# RPi_SPI_outputs_v03.net
KiCad netlist of a schematic drawn in EAGLE
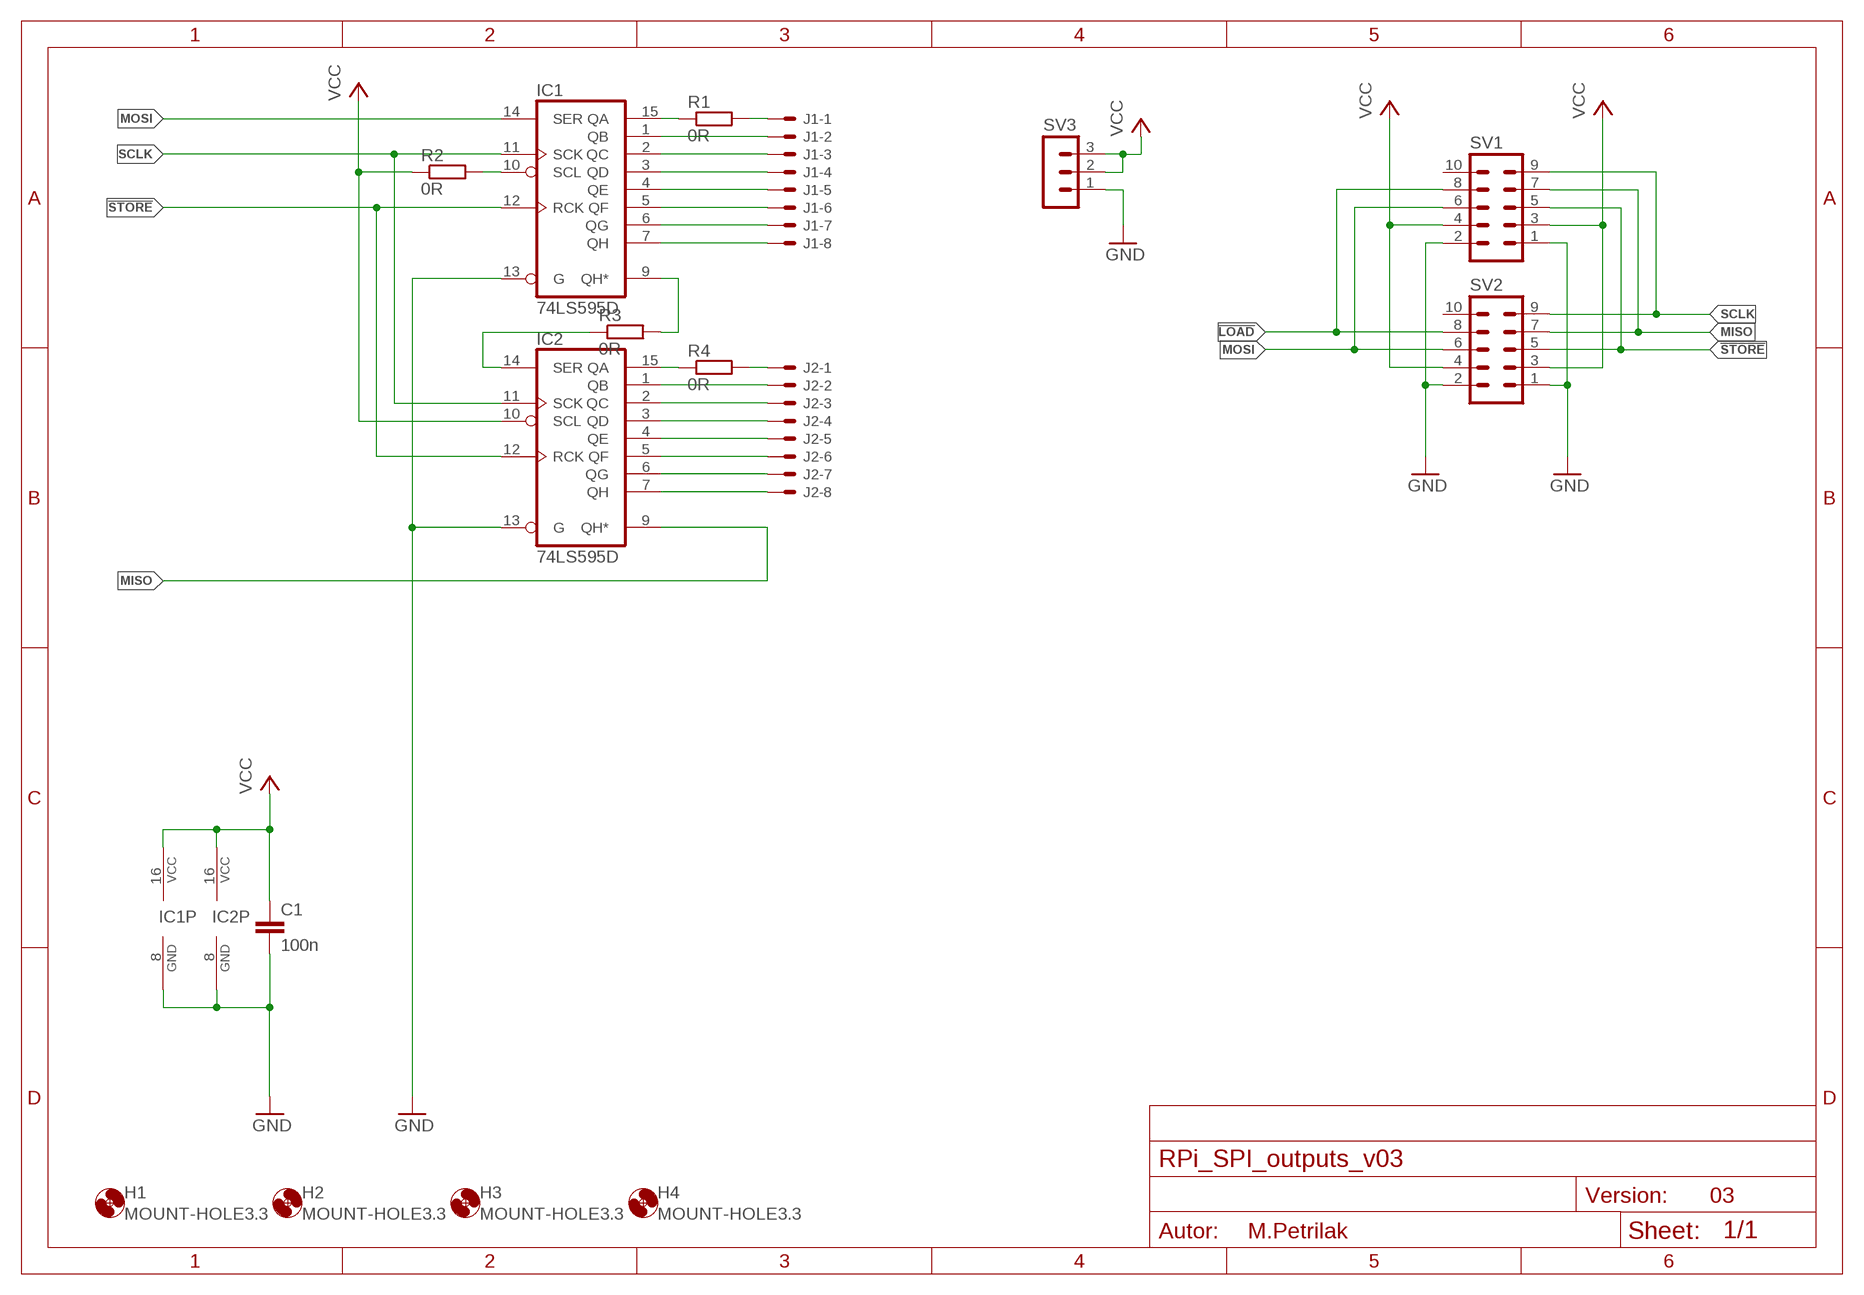
[diagram p0: schematic, sheet 1]

(export (version "E")
  (design (tool "Eeschema 10.0.6"))
  (components
    (comp (ref "C1")
      (value "100n")
      (footprint "eagle-import:C1206")
      (libsource (lib "eagle-import") (part "C-EUC1206"))
    )
    (comp (ref "H1")
      (value "MOUNT-HOLE3.3")
      (footprint "eagle-import:3,3")
      (libsource (lib "eagle-import") (part "MOUNT-HOLE3.3"))
    )
    (comp (ref "H2")
      (value "MOUNT-HOLE3.3")
      (footprint "eagle-import:3,3")
      (libsource (lib "eagle-import") (part "MOUNT-HOLE3.3"))
    )
    (comp (ref "H3")
      (value "MOUNT-HOLE3.3")
      (footprint "eagle-import:3,3")
      (libsource (lib "eagle-import") (part "MOUNT-HOLE3.3"))
    )
    (comp (ref "H4")
      (value "MOUNT-HOLE3.3")
      (footprint "eagle-import:3,3")
      (libsource (lib "eagle-import") (part "MOUNT-HOLE3.3"))
    )
    (comp (ref "IC1")
      (value "74LS595D")
      (footprint "eagle-import:SO16")
      (libsource (lib "eagle-import") (part "74595DLS"))
    )
    (comp (ref "IC2")
      (value "74LS595D")
      (footprint "eagle-import:SO16")
      (libsource (lib "eagle-import") (part "74595DLS"))
    )
    (comp (ref "J1")
      (value "22-05-7088-SPEC-08")
      (footprint "eagle-import:7395-08_SPEC")
      (libsource (lib "eagle-import") (part "22-?-0805-7088-SPEC"))
    )
    (comp (ref "J2")
      (value "22-05-7088-SPEC-08")
      (footprint "eagle-import:7395-08_SPEC")
      (libsource (lib "eagle-import") (part "22-?-0805-7088-SPEC"))
    )
    (comp (ref "R1")
      (value "0R")
      (footprint "eagle-import:R1206")
      (libsource (lib "eagle-import") (part "R-EU_R1206"))
    )
    (comp (ref "R2")
      (value "0R")
      (footprint "eagle-import:R1206")
      (libsource (lib "eagle-import") (part "R-EU_R1206"))
    )
    (comp (ref "R3")
      (value "0R")
      (footprint "eagle-import:R1206")
      (libsource (lib "eagle-import") (part "R-EU_R1206"))
    )
    (comp (ref "R4")
      (value "0R")
      (footprint "eagle-import:R1206")
      (libsource (lib "eagle-import") (part "R-EU_R1206"))
    )
    (comp (ref "SV1")
      (value "ML10")
      (footprint "eagle-import:ML10")
      (libsource (lib "eagle-import") (part "ML10"))
    )
    (comp (ref "SV2")
      (value "ML10")
      (footprint "eagle-import:ML10")
      (libsource (lib "eagle-import") (part "ML10"))
    )
    (comp (ref "SV3")
      (value "MA03-1_NO")
      (footprint "eagle-import:MA03-1_NO")
      (libsource (lib "eagle-import") (part "MA03-1_NO"))
    )
  )
  (nets
    (net (code "1") (name "/~{LOAD}") (class "Default")
      (node (ref "SV1") (pin "8") (pinfunction "8_8") (pintype "passive"))
      (node (ref "SV2") (pin "8") (pinfunction "8_8") (pintype "passive"))
    )
    (net (code "2") (name "/~{STORE}") (class "Default")
      (node (ref "IC1") (pin "12") (pinfunction "RCK_12") (pintype "input"))
      (node (ref "IC2") (pin "12") (pinfunction "RCK_12") (pintype "input"))
      (node (ref "SV1") (pin "5") (pinfunction "5_5") (pintype "passive"))
      (node (ref "SV2") (pin "5") (pinfunction "5_5") (pintype "passive"))
    )
    (net (code "3") (name "GND") (class "Default")
      (node (ref "C1") (pin "2") (pinfunction "2_2") (pintype "passive"))
      (node (ref "IC1") (pin "13") (pinfunction "G_13") (pintype "input"))
      (node (ref "IC1") (pin "8") (pinfunction "GND_8") (pintype "power_in"))
      (node (ref "IC2") (pin "13") (pinfunction "G_13") (pintype "input"))
      (node (ref "IC2") (pin "8") (pinfunction "GND_8") (pintype "power_in"))
      (node (ref "SV1") (pin "1") (pinfunction "1_1") (pintype "passive"))
      (node (ref "SV1") (pin "2") (pinfunction "2_2") (pintype "passive"))
      (node (ref "SV2") (pin "1") (pinfunction "1_1") (pintype "passive"))
      (node (ref "SV2") (pin "2") (pinfunction "2_2") (pintype "passive"))
      (node (ref "SV3") (pin "1") (pinfunction "1_1") (pintype "passive"))
    )
    (net (code "4") (name "MISO") (class "Default")
      (node (ref "IC2") (pin "9") (pinfunction "QH*_9") (pintype "tri_state"))
      (node (ref "SV1") (pin "7") (pinfunction "7_7") (pintype "passive"))
      (node (ref "SV2") (pin "7") (pinfunction "7_7") (pintype "passive"))
    )
    (net (code "5") (name "MOSI") (class "Default")
      (node (ref "IC1") (pin "14") (pinfunction "SER_14") (pintype "input"))
      (node (ref "SV1") (pin "6") (pinfunction "6_6") (pintype "passive"))
      (node (ref "SV2") (pin "6") (pinfunction "6_6") (pintype "passive"))
    )
    (net (code "6") (name "Net-(IC1A-QA)") (class "Default")
      (node (ref "IC1") (pin "15") (pinfunction "QA_15") (pintype "tri_state"))
      (node (ref "R1") (pin "1") (pinfunction "1_1") (pintype "passive"))
    )
    (net (code "7") (name "Net-(IC1A-QB)") (class "Default")
      (node (ref "IC1") (pin "1") (pinfunction "QB_1") (pintype "tri_state"))
      (node (ref "J1") (pin "2") (pinfunction "S_2") (pintype "passive"))
    )
    (net (code "8") (name "Net-(IC1A-QC)") (class "Default")
      (node (ref "IC1") (pin "2") (pinfunction "QC_2") (pintype "tri_state"))
      (node (ref "J1") (pin "3") (pinfunction "S_3") (pintype "passive"))
    )
    (net (code "9") (name "Net-(IC1A-QD)") (class "Default")
      (node (ref "IC1") (pin "3") (pinfunction "QD_3") (pintype "tri_state"))
      (node (ref "J1") (pin "4") (pinfunction "S_4") (pintype "passive"))
    )
    (net (code "10") (name "Net-(IC1A-QE)") (class "Default")
      (node (ref "IC1") (pin "4") (pinfunction "QE_4") (pintype "tri_state"))
      (node (ref "J1") (pin "5") (pinfunction "S_5") (pintype "passive"))
    )
    (net (code "11") (name "Net-(IC1A-QF)") (class "Default")
      (node (ref "IC1") (pin "5") (pinfunction "QF_5") (pintype "tri_state"))
      (node (ref "J1") (pin "6") (pinfunction "S_6") (pintype "passive"))
    )
    (net (code "12") (name "Net-(IC1A-QG)") (class "Default")
      (node (ref "IC1") (pin "6") (pinfunction "QG_6") (pintype "tri_state"))
      (node (ref "J1") (pin "7") (pinfunction "S_7") (pintype "passive"))
    )
    (net (code "13") (name "Net-(IC1A-QH)") (class "Default")
      (node (ref "IC1") (pin "7") (pinfunction "QH_7") (pintype "tri_state"))
      (node (ref "J1") (pin "8") (pinfunction "S_8") (pintype "passive"))
    )
    (net (code "14") (name "Net-(IC1A-QH*)") (class "Default")
      (node (ref "IC1") (pin "9") (pinfunction "QH*_9") (pintype "tri_state"))
      (node (ref "R3") (pin "2") (pinfunction "2_2") (pintype "passive"))
    )
    (net (code "15") (name "Net-(IC1A-SCL)") (class "Default")
      (node (ref "IC1") (pin "10") (pinfunction "SCL_10") (pintype "input"))
      (node (ref "R2") (pin "2") (pinfunction "2_2") (pintype "passive"))
    )
    (net (code "16") (name "Net-(IC2A-QA)") (class "Default")
      (node (ref "IC2") (pin "15") (pinfunction "QA_15") (pintype "tri_state"))
      (node (ref "R4") (pin "1") (pinfunction "1_1") (pintype "passive"))
    )
    (net (code "17") (name "Net-(IC2A-QB)") (class "Default")
      (node (ref "IC2") (pin "1") (pinfunction "QB_1") (pintype "tri_state"))
      (node (ref "J2") (pin "2") (pinfunction "S_2") (pintype "passive"))
    )
    (net (code "18") (name "Net-(IC2A-QC)") (class "Default")
      (node (ref "IC2") (pin "2") (pinfunction "QC_2") (pintype "tri_state"))
      (node (ref "J2") (pin "3") (pinfunction "S_3") (pintype "passive"))
    )
    (net (code "19") (name "Net-(IC2A-QD)") (class "Default")
      (node (ref "IC2") (pin "3") (pinfunction "QD_3") (pintype "tri_state"))
      (node (ref "J2") (pin "4") (pinfunction "S_4") (pintype "passive"))
    )
    (net (code "20") (name "Net-(IC2A-QE)") (class "Default")
      (node (ref "IC2") (pin "4") (pinfunction "QE_4") (pintype "tri_state"))
      (node (ref "J2") (pin "5") (pinfunction "S_5") (pintype "passive"))
    )
    (net (code "21") (name "Net-(IC2A-QF)") (class "Default")
      (node (ref "IC2") (pin "5") (pinfunction "QF_5") (pintype "tri_state"))
      (node (ref "J2") (pin "6") (pinfunction "S_6") (pintype "passive"))
    )
    (net (code "22") (name "Net-(IC2A-QG)") (class "Default")
      (node (ref "IC2") (pin "6") (pinfunction "QG_6") (pintype "tri_state"))
      (node (ref "J2") (pin "7") (pinfunction "S_7") (pintype "passive"))
    )
    (net (code "23") (name "Net-(IC2A-QH)") (class "Default")
      (node (ref "IC2") (pin "7") (pinfunction "QH_7") (pintype "tri_state"))
      (node (ref "J2") (pin "8") (pinfunction "S_8") (pintype "passive"))
    )
    (net (code "24") (name "Net-(IC2A-SER)") (class "Default")
      (node (ref "IC2") (pin "14") (pinfunction "SER_14") (pintype "input"))
      (node (ref "R3") (pin "1") (pinfunction "1_1") (pintype "passive"))
    )
    (net (code "25") (name "Net-(J1A-S)") (class "Default")
      (node (ref "J1") (pin "1") (pinfunction "S_1") (pintype "passive"))
      (node (ref "R1") (pin "2") (pinfunction "2_2") (pintype "passive"))
    )
    (net (code "26") (name "Net-(J2A-S)") (class "Default")
      (node (ref "J2") (pin "1") (pinfunction "S_1") (pintype "passive"))
      (node (ref "R4") (pin "2") (pinfunction "2_2") (pintype "passive"))
    )
    (net (code "27") (name "SCLK") (class "Default")
      (node (ref "IC1") (pin "11") (pinfunction "SCK_11") (pintype "input"))
      (node (ref "IC2") (pin "11") (pinfunction "SCK_11") (pintype "input"))
      (node (ref "SV1") (pin "9") (pinfunction "9_9") (pintype "passive"))
      (node (ref "SV2") (pin "9") (pinfunction "9_9") (pintype "passive"))
    )
    (net (code "28") (name "VCC") (class "Default")
      (node (ref "C1") (pin "1") (pinfunction "1_1") (pintype "passive"))
      (node (ref "IC1") (pin "16") (pinfunction "VCC_16") (pintype "power_in"))
      (node (ref "IC2") (pin "10") (pinfunction "SCL_10") (pintype "input"))
      (node (ref "IC2") (pin "16") (pinfunction "VCC_16") (pintype "power_in"))
      (node (ref "R2") (pin "1") (pinfunction "1_1") (pintype "passive"))
      (node (ref "SV1") (pin "3") (pinfunction "3_3") (pintype "passive"))
      (node (ref "SV1") (pin "4") (pinfunction "4_4") (pintype "passive"))
      (node (ref "SV2") (pin "3") (pinfunction "3_3") (pintype "passive"))
      (node (ref "SV2") (pin "4") (pinfunction "4_4") (pintype "passive"))
      (node (ref "SV3") (pin "2") (pinfunction "2_2") (pintype "passive"))
      (node (ref "SV3") (pin "3") (pinfunction "3_3") (pintype "passive"))
    )
    (net (code "29") (name "unconnected-(SV1-Pad10)") (class "Default")
      (node (ref "SV1") (pin "10") (pinfunction "10_10") (pintype "passive"))
    )
    (net (code "30") (name "unconnected-(SV2-Pad10)") (class "Default")
      (node (ref "SV2") (pin "10") (pinfunction "10_10") (pintype "passive"))
    )
  )
)
